# COMMUNICATION.net
KiCad netlist of a schematic drawn in Altium Designer
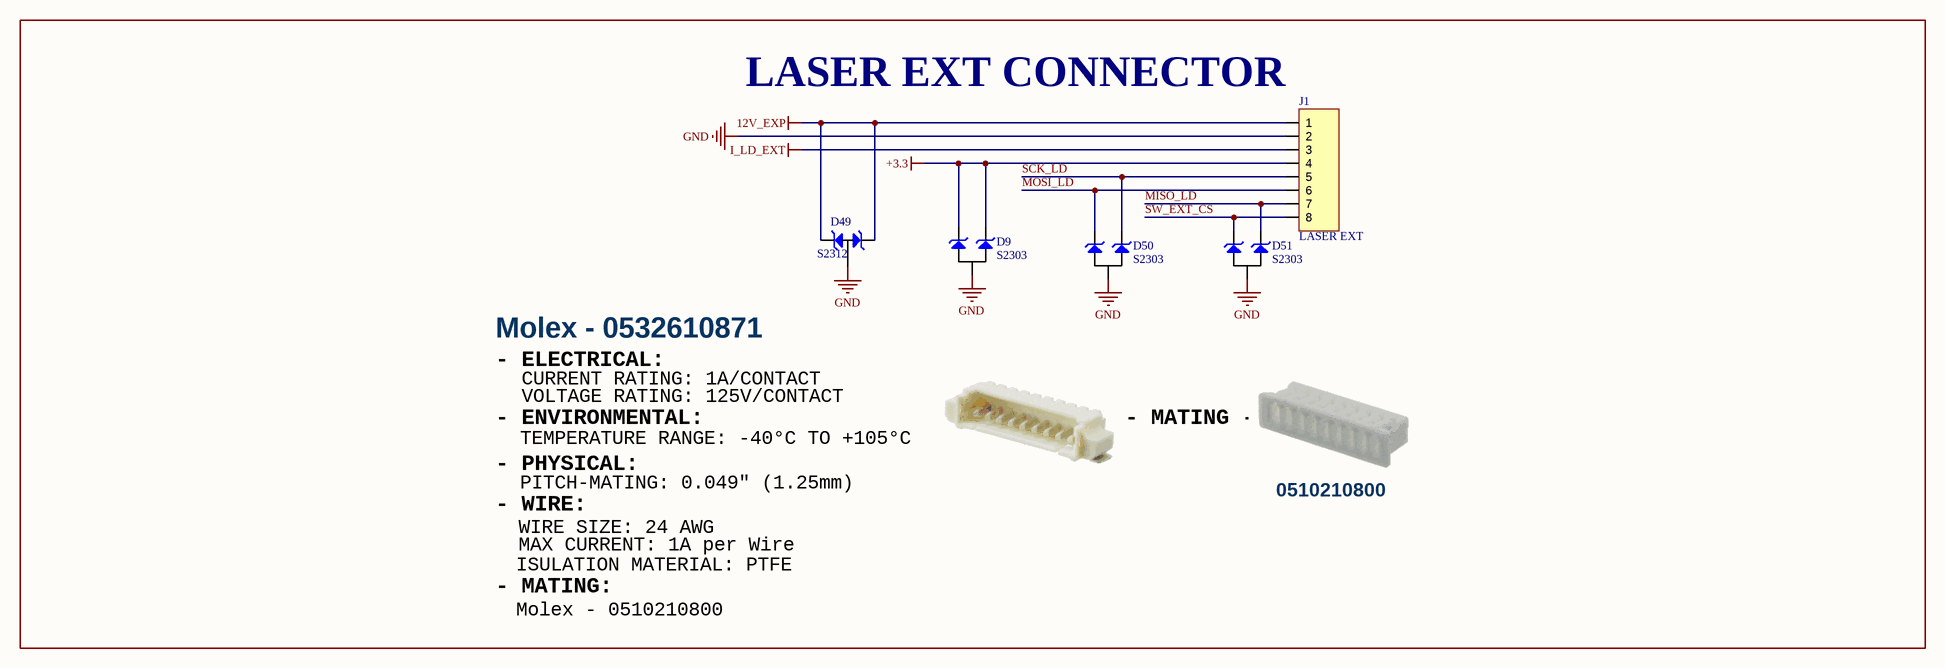
[diagram p0: COMMUNICATION.SchDoc]

(export (version "E")
  (design (tool "Eeschema 10.0.6"))
  (components
    (comp (ref "D9")
      (value "S2303")
      (footprint "SOT23-123")
      (description "TVS DIODE 3.3VWM 8VC SOT23, P/N:  \r\nS2303")
      (libsource (lib "Library") (part "S2303"))
    )
    (comp (ref "D49")
      (value "S2312")
      (footprint "SOT23-123")
      (description "TVS DIODE 12VWM 19VC SOT23, P/N:  S2312")
      (libsource (lib "Library") (part "S2315"))
    )
    (comp (ref "D50")
      (value "S2303")
      (footprint "SOT23-123")
      (description "TVS DIODE 3.3VWM 8VC SOT23, P/N:  \r\nS2303")
      (libsource (lib "Library") (part "S2303"))
    )
    (comp (ref "D51")
      (value "S2303")
      (footprint "SOT23-123")
      (description "TVS DIODE 3.3VWM 8VC SOT23, P/N:  \r\nS2303")
      (libsource (lib "Library") (part "S2303"))
    )
    (comp (ref "J1")
      (value "LASER EXT")
      (footprint "0532610871")
      (description "WR-PHD 2.54 mm Angled Socket Header")
      (fields
        (field (name "MANUFACTURER") "Würth Elektronik eiSos GmbH")
        (field (name "PARTNO") "613008143121")
        (field (name "CREATED BY") "Karrer Zheng")
      )
      (libsource (lib "Library_HUNG") (part "JP8"))
    )
  )
  (nets
    (net (code "1") (name "+3.3") (class "Default")
      (node (ref "D9") (pin "1") (pintype "passive"))
      (node (ref "D9") (pin "3") (pintype "passive"))
      (node (ref "J1") (pin "4") (pinfunction "4_4") (pintype "passive"))
    )
    (net (code "2") (name "/MISO_LD") (class "Default")
      (node (ref "D51") (pin "3") (pintype "passive"))
      (node (ref "J1") (pin "7") (pinfunction "7_7") (pintype "passive"))
    )
    (net (code "3") (name "/MOSI_LD") (class "Default")
      (node (ref "D50") (pin "1") (pintype "passive"))
      (node (ref "J1") (pin "6") (pinfunction "6_6") (pintype "passive"))
    )
    (net (code "4") (name "/SCK_LD") (class "Default")
      (node (ref "D50") (pin "3") (pintype "passive"))
      (node (ref "J1") (pin "5") (pinfunction "5_5") (pintype "passive"))
    )
    (net (code "5") (name "/SW_EXT_CS") (class "Default")
      (node (ref "D51") (pin "1") (pintype "passive"))
      (node (ref "J1") (pin "8") (pinfunction "8_8") (pintype "passive"))
    )
    (net (code "6") (name "12V_EXP") (class "Default")
      (node (ref "D49") (pin "1") (pintype "passive"))
      (node (ref "D49") (pin "3") (pintype "passive"))
      (node (ref "J1") (pin "1") (pinfunction "1_1") (pintype "passive"))
    )
    (net (code "7") (name "GND") (class "Default")
      (node (ref "D49") (pin "2") (pintype "passive"))
      (node (ref "D50") (pin "2") (pintype "passive"))
      (node (ref "D51") (pin "2") (pintype "passive"))
      (node (ref "D9") (pin "2") (pintype "passive"))
      (node (ref "J1") (pin "2") (pinfunction "2_2") (pintype "passive"))
    )
    (net (code "8") (name "I_LD_EXT") (class "Default")
      (node (ref "J1") (pin "3") (pinfunction "3_3") (pintype "passive"))
    )
  )
)
